# 11_mPCIe_CONN.net
KiCad netlist of a schematic drawn in Altium Designer
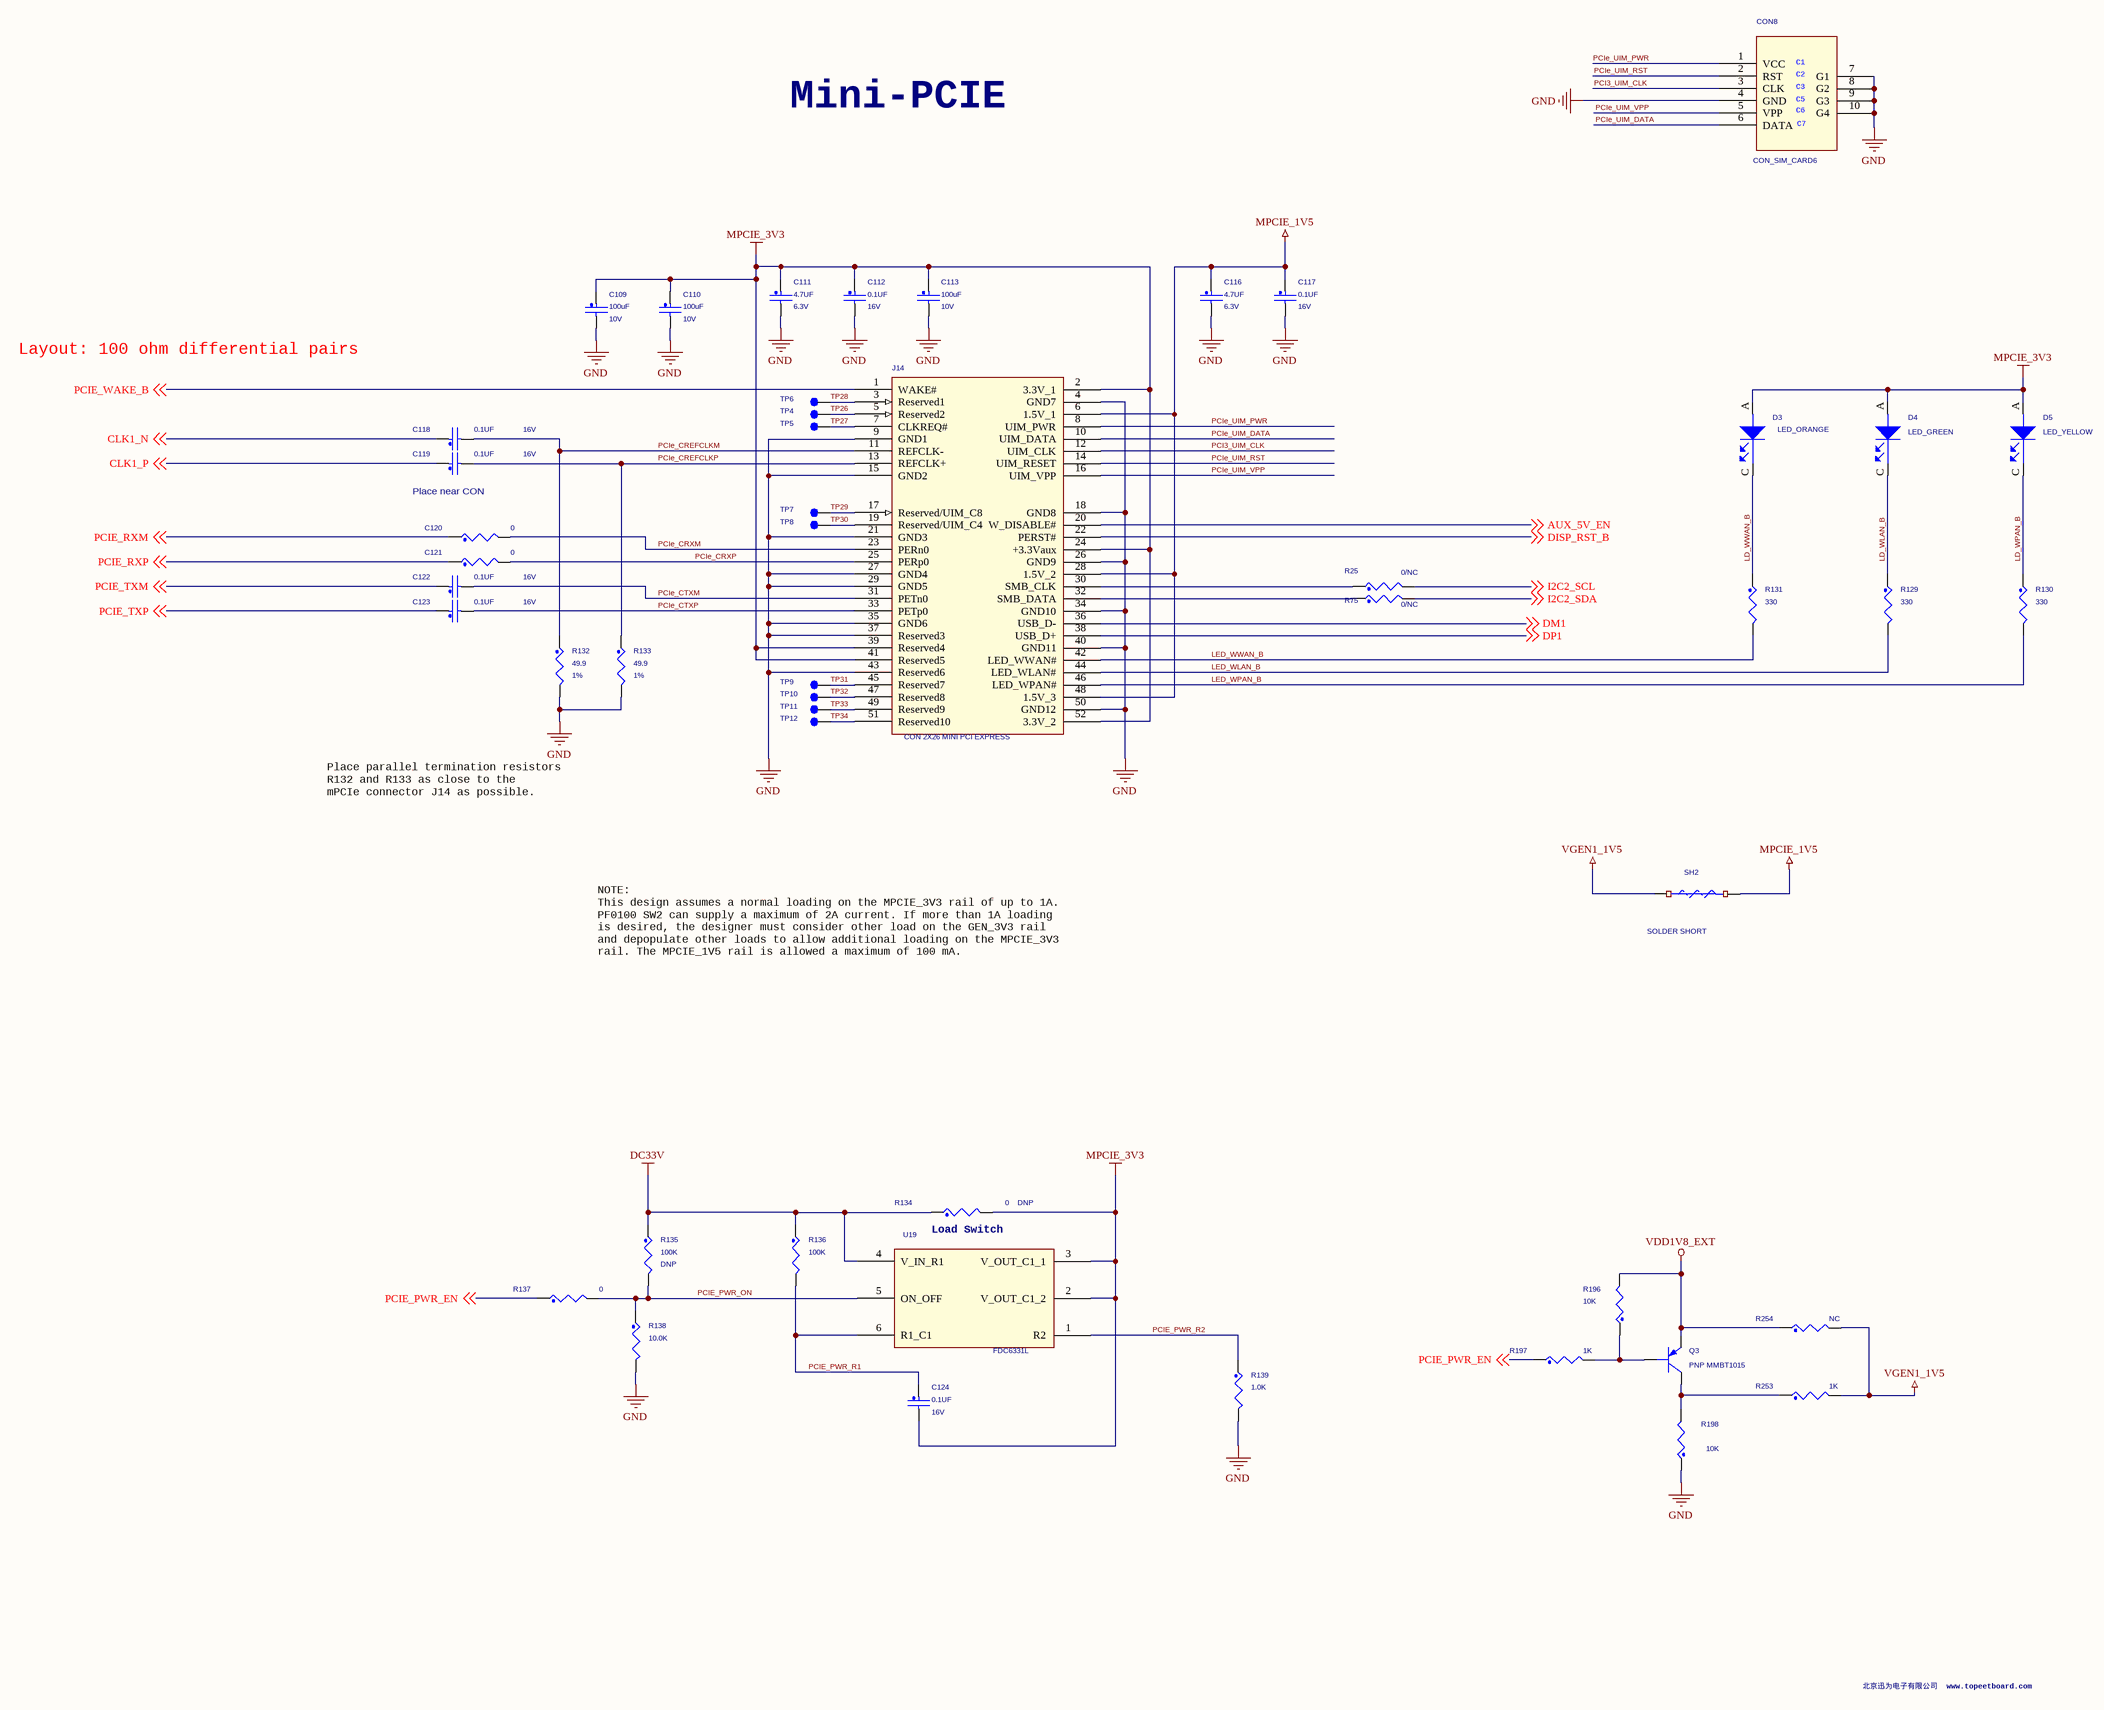
[diagram p0: 11 mPCIe CONN.SchDoc]

(export (version "E")
  (design (tool "Eeschema 10.0.6"))
  (components
    (comp (ref "C109")
      (value "100uF")
      (description "CAP CER 100uF 10V 20% X5R 1206")
      (fields (field (name "WVDC") "10V") (field (name "TOLERANCE") "20%") (field (name "VOLTAGE") "10V"))
      (libsource (lib "*") (part "CAP_NP"))
    )
    (comp (ref "C110")
      (value "100uF")
      (description "CAP CER 100uF 10V 20% X5R 1206")
      (fields (field (name "WVDC") "10V") (field (name "TOLERANCE") "20%") (field (name "VOLTAGE") "10V"))
      (libsource (lib "*") (part "CAP_NP"))
    )
    (comp (ref "C111")
      (value "4.7UF")
      (description "CAP CER 4.7UF 6.3V 10% X5R 0603")
      (fields (field (name "VOLTAGE") "6.3V") (field (name "TOLERANCE") "10%") (field (name "WVDC") "6.3V"))
      (libsource (lib "*") (part "CAP_NP"))
    )
    (comp (ref "C112")
      (value "0.1UF")
      (description "CAP CER 0.1UF 16V 10% X7R 0402")
      (fields (field (name "VOLTAGE") "16V") (field (name "TOLERANCE") "10%") (field (name "WVDC") "16V"))
      (libsource (lib "*") (part "CAP_NP"))
    )
    (comp (ref "C113")
      (value "100uF")
      (description "CAP CER 100uF 10V 20% X5R 1206")
      (fields (field (name "WVDC") "10V") (field (name "TOLERANCE") "20%") (field (name "VOLTAGE") "10V"))
      (libsource (lib "*") (part "CAP_NP"))
    )
    (comp (ref "C116")
      (value "4.7UF")
      (description "CAP CER 4.7UF 6.3V 10% X5R 0603")
      (fields (field (name "VOLTAGE") "6.3V") (field (name "TOLERANCE") "10%") (field (name "WVDC") "6.3V"))
      (libsource (lib "*") (part "CAP_NP"))
    )
    (comp (ref "C117")
      (value "0.1UF")
      (description "CAP CER 0.1UF 16V 10% X7R 0402")
      (fields (field (name "VOLTAGE") "16V") (field (name "WVDC") "16V") (field (name "TOLERANCE") "10%"))
      (libsource (lib "*") (part "CAP_NP"))
    )
    (comp (ref "C118")
      (value "0.1UF")
      (description "CAP CER 0.1UF 16V 10% X7R 0402")
      (fields (field (name "VOLTAGE") "16V") (field (name "WVDC") "16V") (field (name "TOLERANCE") "10%"))
      (libsource (lib "*") (part "CAP_NP"))
    )
    (comp (ref "C119")
      (value "0.1UF")
      (description "CAP CER 0.1UF 16V 10% X7R 0402")
      (fields (field (name "VOLTAGE") "16V") (field (name "WVDC") "16V") (field (name "TOLERANCE") "10%"))
      (libsource (lib "*") (part "CAP_NP"))
    )
    (comp (ref "C120")
      (value "0")
      (description "RES MF ZERO OHM 1/10W -- 0402")
      (libsource (lib "*") (part "RES_Dup1"))
    )
    (comp (ref "C121")
      (value "0")
      (description "RES MF ZERO OHM 1/10W -- 0402")
      (libsource (lib "*") (part "RES_Dup1"))
    )
    (comp (ref "C122")
      (value "0.1UF")
      (description "CAP CER 0.1UF 16V 10% X7R 0402")
      (fields (field (name "VOLTAGE") "16V") (field (name "WVDC") "16V") (field (name "TOLERANCE") "10%"))
      (libsource (lib "*") (part "CAP_NP"))
    )
    (comp (ref "C123")
      (value "0.1UF")
      (description "CAP CER 0.1UF 16V 10% X7R 0402")
      (fields (field (name "VOLTAGE") "16V") (field (name "WVDC") "16V") (field (name "TOLERANCE") "10%"))
      (libsource (lib "*") (part "CAP_NP"))
    )
    (comp (ref "C124")
      (value "0.1UF")
      (description "CAP CER 0.1UF 16V 10% X7R 0402")
      (fields (field (name "VOLTAGE") "16V") (field (name "TOLERANCE") "10%") (field (name "WVDC") "16V"))
      (libsource (lib "*") (part "CAP_NP"))
    )
    (comp (ref "CON8")
      (value "CON_SIM_CARD6")
      (footprint "SIM_CARD6")
      (libsource (lib "*") (part "CON_SIM_CARD6_2"))
    )
    (comp (ref "D3")
      (value "LED_ORANGE")
      (description "LED SUPER BRIGHT ORANGE SMD 0603")
      (libsource (lib "*") (part "LED"))
    )
    (comp (ref "D4")
      (value "LED_GREEN")
      (description "LED ULTRA-BRIGHT GREEN SMT 0603")
      (libsource (lib "*") (part "LED"))
    )
    (comp (ref "D5")
      (value "LED_YELLOW")
      (description "LED ULTRA-BRIGHT YELLOW 30MA 5V SMT 0603")
      (libsource (lib "*") (part "LED"))
    )
    (comp (ref "J14")
      (value "CON 2X26 MINI PCI EXPRESS")
      (description "CON 2X26 MINI PCI EXPRESS SMT 0.8MM SP 1136H")
      (libsource (lib "*") (part "MINI_PCI_LATCH_52P"))
    )
    (comp (ref "Q3") (value "PNP MMBT1015") (libsource (lib "*") (part "PNP ECB")))
    (comp (ref "R25")
      (value "0/NC")
      (description "RES MF 330 OHM 1/16W 1% AEC-Q200 0402")
      (fields (field (name "TOLERANCE") "1%"))
      (libsource (lib "*") (part "RES_Dup1"))
    )
    (comp (ref "R75")
      (value "0/NC")
      (description "RES MF 330 OHM 1/16W 1% AEC-Q200 0402")
      (fields (field (name "TOLERANCE") "1%"))
      (libsource (lib "*") (part "RES_Dup1"))
    )
    (comp (ref "R129")
      (value "330")
      (description "RES MF 330 OHM 1/16W 1% AEC-Q200 0402")
      (fields (field (name "TOLERANCE") "1%"))
      (libsource (lib "*") (part "RES_Dup1"))
    )
    (comp (ref "R130")
      (value "330")
      (description "RES MF 330 OHM 1/16W 1% AEC-Q200 0402")
      (fields (field (name "TOLERANCE") "1%"))
      (libsource (lib "*") (part "RES_Dup1"))
    )
    (comp (ref "R131")
      (value "330")
      (description "RES MF 330 OHM 1/16W 1% AEC-Q200 0402")
      (fields (field (name "TOLERANCE") "1%"))
      (libsource (lib "*") (part "RES_Dup1"))
    )
    (comp (ref "R132")
      (value "49.9")
      (description "RES MF 49.9 OHM 1/16W 1% 0402")
      (fields (field (name "TOLERANCE") "1%"))
      (libsource (lib "*") (part "RES_Dup1"))
    )
    (comp (ref "R133")
      (value "49.9")
      (description "RES MF 49.9 OHM 1/16W 1% 0402")
      (fields (field (name "TOLERANCE") "1%"))
      (libsource (lib "*") (part "RES_Dup1"))
    )
    (comp (ref "R134")
      (value "0")
      (description "RES MF ZERO OHM 1/10W -- 0402")
      (fields (field (name "ASSY_OPT") "DNP"))
      (libsource (lib "*") (part "RES_Dup1"))
    )
    (comp (ref "R135")
      (value "100K")
      (description "RES MF 100K 1/16W 1% 0402")
      (fields (field (name "TOLERANCE") "1%") (field (name "ASSY_OPT") "DNP"))
      (libsource (lib "*") (part "RES_Dup1"))
    )
    (comp (ref "R136")
      (value "100K")
      (description "RES MF 100K 1/16W 1% 0402")
      (fields (field (name "TOLERANCE") "1%"))
      (libsource (lib "*") (part "RES_Dup1"))
    )
    (comp (ref "R137")
      (value "0")
      (description "RES MF ZERO OHM 1/10W -- 0402")
      (libsource (lib "*") (part "RES_Dup1"))
    )
    (comp (ref "R138")
      (value "10.0K")
      (description "RES MF 10.0K 1/16W 1% AEC-Q200 0402")
      (fields (field (name "TOLERANCE") "1%"))
      (libsource (lib "*") (part "RES_Dup1"))
    )
    (comp (ref "R139")
      (value "1.0K")
      (description "RES MF 1.0K 1/16W 1% 0402")
      (fields (field (name "TOLERANCE") "1%"))
      (libsource (lib "*") (part "RES_Dup1"))
    )
    (comp (ref "R196")
      (value "10K")
      (description "RES MF ZERO OHM 1/10W -- 0402")
      (libsource (lib "*") (part "RES_Dup1"))
    )
    (comp (ref "R197")
      (value "1K")
      (description "RES MF ZERO OHM 1/10W -- 0402")
      (libsource (lib "*") (part "RES_Dup1"))
    )
    (comp (ref "R198")
      (value "10K")
      (description "RES MF ZERO OHM 1/10W -- 0402")
      (libsource (lib "*") (part "RES_Dup1"))
    )
    (comp (ref "R253")
      (value "1K")
      (description "RES MF ZERO OHM 1/10W -- 0402")
      (libsource (lib "*") (part "RES_Dup1"))
    )
    (comp (ref "R254")
      (value "NC")
      (description "RES MF ZERO OHM 1/10W -- 0402")
      (libsource (lib "*") (part "RES_Dup1"))
    )
    (comp (ref "SH2")
      (value "SOLDER SHORT")
      (description "SOLDER SHORT 0805  SMT NO PART TO ORDER")
      (libsource (lib "*") (part "RES_SHORT-2"))
    )
    (comp (ref "TP4")
      (value "TEST POINT")
      (description "TEST POINT PAD 35 MIL SMT, NO PART TO ORDER")
      (libsource (lib "*") (part "Test pad"))
    )
    (comp (ref "TP5")
      (value "TEST POINT")
      (description "TEST POINT PAD 35 MIL SMT, NO PART TO ORDER")
      (libsource (lib "*") (part "Test pad"))
    )
    (comp (ref "TP6")
      (value "TEST POINT")
      (description "TEST POINT PAD 35 MIL SMT, NO PART TO ORDER")
      (libsource (lib "*") (part "Test pad"))
    )
    (comp (ref "TP7")
      (value "TEST POINT")
      (description "TEST POINT PAD 35 MIL SMT, NO PART TO ORDER")
      (libsource (lib "*") (part "Test pad"))
    )
    (comp (ref "TP8")
      (value "TEST POINT")
      (description "TEST POINT PAD 35 MIL SMT, NO PART TO ORDER")
      (libsource (lib "*") (part "Test pad"))
    )
    (comp (ref "TP9")
      (value "TEST POINT")
      (description "TEST POINT PAD 35 MIL SMT, NO PART TO ORDER")
      (libsource (lib "*") (part "Test pad"))
    )
    (comp (ref "TP10")
      (value "TEST POINT")
      (description "TEST POINT PAD 35 MIL SMT, NO PART TO ORDER")
      (libsource (lib "*") (part "Test pad"))
    )
    (comp (ref "TP11")
      (value "TEST POINT")
      (description "TEST POINT PAD 35 MIL SMT, NO PART TO ORDER")
      (libsource (lib "*") (part "Test pad"))
    )
    (comp (ref "TP12")
      (value "TEST POINT")
      (description "TEST POINT PAD 35 MIL SMT, NO PART TO ORDER")
      (libsource (lib "*") (part "Test pad"))
    )
    (comp (ref "U19")
      (value "FDC6331L")
      (description "IC LOAD SW 2.5-8V SSOT6")
      (libsource (lib "*") (part "FDC6331L"))
    )
  )
  (nets
    (net (code "1") (name "/LD_WLAN_B") (class "Default")
      (node (ref "D4") (pin "C") (pinfunction "CATHODE_C") (pintype "passive"))
      (node (ref "R129") (pin "1") (pinfunction "1_1") (pintype "passive"))
    )
    (net (code "2") (name "/LD_WPAN_B") (class "Default")
      (node (ref "D5") (pin "C") (pinfunction "CATHODE_C") (pintype "passive"))
      (node (ref "R130") (pin "1") (pinfunction "1_1") (pintype "passive"))
    )
    (net (code "3") (name "/LD_WWAN_B") (class "Default")
      (node (ref "D3") (pin "C") (pinfunction "CATHODE_C") (pintype "passive"))
      (node (ref "R131") (pin "1") (pinfunction "1_1") (pintype "passive"))
    )
    (net (code "4") (name "/LED_WLAN_B") (class "Default")
      (node (ref "J14") (pin "44") (pinfunction "LED_WLAN#_44") (pintype "passive"))
      (node (ref "R129") (pin "2") (pinfunction "2_2") (pintype "passive"))
    )
    (net (code "5") (name "/LED_WPAN_B") (class "Default")
      (node (ref "J14") (pin "46") (pinfunction "LED_WPAN#_46") (pintype "passive"))
      (node (ref "R130") (pin "2") (pinfunction "2_2") (pintype "passive"))
    )
    (net (code "6") (name "/LED_WWAN_B") (class "Default")
      (node (ref "J14") (pin "42") (pinfunction "LED_WWAN#_42") (pintype "passive"))
      (node (ref "R131") (pin "2") (pinfunction "2_2") (pintype "passive"))
    )
    (net (code "7") (name "/PCI3_UIM_CLK") (class "Default")
      (node (ref "CON8") (pin "3") (pinfunction "CLK_3") (pintype "passive"))
      (node (ref "J14") (pin "12") (pinfunction "UIM_CLK_12") (pintype "passive"))
    )
    (net (code "8") (name "/PCIE_PWR_ON") (class "Default")
      (node (ref "R135") (pin "2") (pinfunction "2_2") (pintype "passive"))
      (node (ref "R137") (pin "2") (pinfunction "2_2") (pintype "passive"))
      (node (ref "R138") (pin "1") (pinfunction "1_1") (pintype "passive"))
      (node (ref "U19") (pin "5") (pinfunction "ON_OFF_5") (pintype "passive"))
    )
    (net (code "9") (name "/PCIE_PWR_R1") (class "Default")
      (node (ref "C124") (pin "1") (pinfunction "1_1") (pintype "passive"))
      (node (ref "R136") (pin "2") (pinfunction "2_2") (pintype "passive"))
      (node (ref "U19") (pin "6") (pinfunction "R1_C1_6") (pintype "passive"))
    )
    (net (code "10") (name "/PCIE_PWR_R2") (class "Default")
      (node (ref "R139") (pin "1") (pinfunction "1_1") (pintype "passive"))
      (node (ref "U19") (pin "1") (pinfunction "R2_1") (pintype "passive"))
    )
    (net (code "11") (name "/PCIe_CREFCLKM") (class "Default")
      (node (ref "C118") (pin "2") (pinfunction "2_2") (pintype "passive"))
      (node (ref "J14") (pin "11") (pinfunction "REFCLK-_11") (pintype "passive"))
      (node (ref "R132") (pin "1") (pinfunction "1_1") (pintype "passive"))
    )
    (net (code "12") (name "/PCIe_CREFCLKP") (class "Default")
      (node (ref "C119") (pin "2") (pinfunction "2_2") (pintype "passive"))
      (node (ref "J14") (pin "13") (pinfunction "REFCLK+_13") (pintype "passive"))
      (node (ref "R133") (pin "1") (pinfunction "1_1") (pintype "passive"))
    )
    (net (code "13") (name "/PCIe_CRXM") (class "Default")
      (node (ref "C120") (pin "2") (pinfunction "2_2") (pintype "passive"))
      (node (ref "J14") (pin "23") (pinfunction "PERn0_23") (pintype "passive"))
    )
    (net (code "14") (name "/PCIe_CRXP") (class "Default")
      (node (ref "C121") (pin "2") (pinfunction "2_2") (pintype "passive"))
      (node (ref "J14") (pin "25") (pinfunction "PERp0_25") (pintype "passive"))
    )
    (net (code "15") (name "/PCIe_CTXM") (class "Default")
      (node (ref "C122") (pin "2") (pinfunction "2_2") (pintype "passive"))
      (node (ref "J14") (pin "31") (pinfunction "PETn0_31") (pintype "passive"))
    )
    (net (code "16") (name "/PCIe_CTXP") (class "Default")
      (node (ref "C123") (pin "2") (pinfunction "2_2") (pintype "passive"))
      (node (ref "J14") (pin "33") (pinfunction "PETp0_33") (pintype "passive"))
    )
    (net (code "17") (name "/PCIe_UIM_DATA") (class "Default")
      (node (ref "CON8") (pin "6") (pinfunction "DATA_6") (pintype "passive"))
      (node (ref "J14") (pin "10") (pinfunction "UIM_DATA_10") (pintype "passive"))
    )
    (net (code "18") (name "/PCIe_UIM_PWR") (class "Default")
      (node (ref "CON8") (pin "1") (pinfunction "VCC_1") (pintype "passive"))
      (node (ref "J14") (pin "8") (pinfunction "UIM_PWR_8") (pintype "passive"))
    )
    (net (code "19") (name "/PCIe_UIM_RST") (class "Default")
      (node (ref "CON8") (pin "2") (pinfunction "RST_2") (pintype "passive"))
      (node (ref "J14") (pin "14") (pinfunction "UIM_RESET_14") (pintype "passive"))
    )
    (net (code "20") (name "/PCIe_UIM_VPP") (class "Default")
      (node (ref "CON8") (pin "5") (pinfunction "VPP_5") (pintype "passive"))
      (node (ref "J14") (pin "16") (pinfunction "UIM_VPP_16") (pintype "passive"))
    )
    (net (code "21") (name "/TP26") (class "Default")
      (node (ref "J14") (pin "5") (pinfunction "Reserved2_5") (pintype "input"))
      (node (ref "TP4") (pin "1") (pinfunction "Pin1_1") (pintype "passive"))
    )
    (net (code "22") (name "/TP27") (class "Default")
      (node (ref "J14") (pin "7") (pinfunction "CLKREQ#_7") (pintype "passive"))
      (node (ref "TP5") (pin "1") (pinfunction "Pin1_1") (pintype "passive"))
    )
    (net (code "23") (name "/TP28") (class "Default")
      (node (ref "J14") (pin "3") (pinfunction "Reserved1_3") (pintype "input"))
      (node (ref "TP6") (pin "1") (pinfunction "Pin1_1") (pintype "passive"))
    )
    (net (code "24") (name "/TP29") (class "Default")
      (node (ref "J14") (pin "17") (pinfunction "Reserved/UIM_C8_17") (pintype "input"))
      (node (ref "TP7") (pin "1") (pinfunction "Pin1_1") (pintype "passive"))
    )
    (net (code "25") (name "/TP30") (class "Default")
      (node (ref "J14") (pin "19") (pinfunction "Reserved/UIM_C4_19") (pintype "passive"))
      (node (ref "TP8") (pin "1") (pinfunction "Pin1_1") (pintype "passive"))
    )
    (net (code "26") (name "/TP31") (class "Default")
      (node (ref "J14") (pin "45") (pinfunction "Reserved7_45") (pintype "passive"))
      (node (ref "TP9") (pin "1") (pinfunction "Pin1_1") (pintype "passive"))
    )
    (net (code "27") (name "/TP32") (class "Default")
      (node (ref "J14") (pin "47") (pinfunction "Reserved8_47") (pintype "passive"))
      (node (ref "TP10") (pin "1") (pinfunction "Pin1_1") (pintype "passive"))
    )
    (net (code "28") (name "/TP33") (class "Default")
      (node (ref "J14") (pin "49") (pinfunction "Reserved9_49") (pintype "passive"))
      (node (ref "TP11") (pin "1") (pinfunction "Pin1_1") (pintype "passive"))
    )
    (net (code "29") (name "/TP34") (class "Default")
      (node (ref "J14") (pin "51") (pinfunction "Reserved10_51") (pintype "passive"))
      (node (ref "TP12") (pin "1") (pinfunction "Pin1_1") (pintype "passive"))
    )
    (net (code "30") (name "AUX_5V_EN") (class "Default")
      (node (ref "J14") (pin "20") (pinfunction "W_DISABLE#_20") (pintype "passive"))
    )
    (net (code "31") (name "CLK1_N") (class "Default")
      (node (ref "C118") (pin "1") (pinfunction "1_1") (pintype "passive"))
    )
    (net (code "32") (name "CLK1_P") (class "Default")
      (node (ref "C119") (pin "1") (pinfunction "1_1") (pintype "passive"))
    )
    (net (code "33") (name "DC33V") (class "Default")
      (node (ref "R134") (pin "1") (pinfunction "1_1") (pintype "passive"))
      (node (ref "R135") (pin "1") (pinfunction "1_1") (pintype "passive"))
      (node (ref "R136") (pin "1") (pinfunction "1_1") (pintype "passive"))
      (node (ref "U19") (pin "4") (pinfunction "V_IN_R1_4") (pintype "passive"))
    )
    (net (code "34") (name "DISP_RST_B") (class "Default")
      (node (ref "J14") (pin "22") (pinfunction "PERST#_22") (pintype "passive"))
    )
    (net (code "35") (name "DM1") (class "Default")
      (node (ref "J14") (pin "36") (pinfunction "USB_D-_36") (pintype "passive"))
    )
    (net (code "36") (name "DP1") (class "Default")
      (node (ref "J14") (pin "38") (pinfunction "USB_D+_38") (pintype "passive"))
    )
    (net (code "37") (name "GND") (class "Default")
      (node (ref "C109") (pin "2") (pinfunction "2_2") (pintype "passive"))
      (node (ref "C110") (pin "2") (pinfunction "2_2") (pintype "passive"))
      (node (ref "C111") (pin "2") (pinfunction "2_2") (pintype "passive"))
      (node (ref "C112") (pin "2") (pinfunction "2_2") (pintype "passive"))
      (node (ref "C113") (pin "2") (pinfunction "2_2") (pintype "passive"))
      (node (ref "C116") (pin "2") (pinfunction "2_2") (pintype "passive"))
      (node (ref "C117") (pin "2") (pinfunction "2_2") (pintype "passive"))
      (node (ref "CON8") (pin "10") (pinfunction "G4_10") (pintype "passive"))
      (node (ref "CON8") (pin "4") (pinfunction "GND_4") (pintype "passive"))
      (node (ref "CON8") (pin "7") (pinfunction "G1_7") (pintype "passive"))
      (node (ref "CON8") (pin "8") (pinfunction "G2_8") (pintype "passive"))
      (node (ref "CON8") (pin "9") (pinfunction "G3_9") (pintype "passive"))
      (node (ref "J14") (pin "15") (pinfunction "GND2_15") (pintype "passive"))
      (node (ref "J14") (pin "18") (pinfunction "GND8_18") (pintype "passive"))
      (node (ref "J14") (pin "21") (pinfunction "GND3_21") (pintype "passive"))
      (node (ref "J14") (pin "26") (pinfunction "GND9_26") (pintype "passive"))
      (node (ref "J14") (pin "27") (pinfunction "GND4_27") (pintype "passive"))
      (node (ref "J14") (pin "29") (pinfunction "GND5_29") (pintype "passive"))
      (node (ref "J14") (pin "34") (pinfunction "GND10_34") (pintype "passive"))
      (node (ref "J14") (pin "35") (pinfunction "GND6_35") (pintype "passive"))
      (node (ref "J14") (pin "37") (pinfunction "Reserved3_37") (pintype "passive"))
      (node (ref "J14") (pin "4") (pinfunction "GND7_4") (pintype "passive"))
      (node (ref "J14") (pin "40") (pinfunction "GND11_40") (pintype "passive"))
      (node (ref "J14") (pin "43") (pinfunction "Reserved6_43") (pintype "passive"))
      (node (ref "J14") (pin "50") (pinfunction "GND12_50") (pintype "passive"))
      (node (ref "J14") (pin "9") (pinfunction "GND1_9") (pintype "passive"))
      (node (ref "R132") (pin "2") (pinfunction "2_2") (pintype "passive"))
      (node (ref "R133") (pin "2") (pinfunction "2_2") (pintype "passive"))
      (node (ref "R138") (pin "2") (pinfunction "2_2") (pintype "passive"))
      (node (ref "R139") (pin "2") (pinfunction "2_2") (pintype "passive"))
      (node (ref "R198") (pin "1") (pinfunction "1_1") (pintype "passive"))
    )
    (net (code "38") (name "I2C2_SCL") (class "Default")
      (node (ref "R25") (pin "2") (pinfunction "2_2") (pintype "passive"))
    )
    (net (code "39") (name "I2C2_SDA") (class "Default")
      (node (ref "R75") (pin "2") (pinfunction "2_2") (pintype "passive"))
    )
    (net (code "40") (name "MPCIE_1V5") (class "Default")
      (node (ref "C116") (pin "1") (pinfunction "1_1") (pintype "passive"))
      (node (ref "C117") (pin "1") (pinfunction "1_1") (pintype "passive"))
      (node (ref "J14") (pin "28") (pinfunction "1.5V_2_28") (pintype "passive"))
      (node (ref "J14") (pin "48") (pinfunction "1.5V_3_48") (pintype "passive"))
      (node (ref "J14") (pin "6") (pinfunction "1.5V_1_6") (pintype "passive"))
      (node (ref "SH2") (pin "2") (pinfunction "2_2") (pintype "passive"))
    )
    (net (code "41") (name "MPCIE_3V3") (class "Default")
      (node (ref "C109") (pin "1") (pinfunction "1_1") (pintype "passive"))
      (node (ref "C110") (pin "1") (pinfunction "1_1") (pintype "passive"))
      (node (ref "C111") (pin "1") (pinfunction "1_1") (pintype "passive"))
      (node (ref "C112") (pin "1") (pinfunction "1_1") (pintype "passive"))
      (node (ref "C113") (pin "1") (pinfunction "1_1") (pintype "passive"))
      (node (ref "C124") (pin "2") (pinfunction "2_2") (pintype "passive"))
      (node (ref "D3") (pin "A") (pinfunction "ANODE_A") (pintype "passive"))
      (node (ref "D4") (pin "A") (pinfunction "ANODE_A") (pintype "passive"))
      (node (ref "D5") (pin "A") (pinfunction "ANODE_A") (pintype "passive"))
      (node (ref "J14") (pin "2") (pinfunction "3.3V_1_2") (pintype "passive"))
      (node (ref "J14") (pin "24") (pinfunction "+3.3Vaux_24") (pintype "passive"))
      (node (ref "J14") (pin "39") (pinfunction "Reserved4_39") (pintype "passive"))
      (node (ref "J14") (pin "41") (pinfunction "Reserved5_41") (pintype "passive"))
      (node (ref "J14") (pin "52") (pinfunction "3.3V_2_52") (pintype "passive"))
      (node (ref "R134") (pin "2") (pinfunction "2_2") (pintype "passive"))
      (node (ref "U19") (pin "2") (pinfunction "V_OUT_C1_2_2") (pintype "passive"))
      (node (ref "U19") (pin "3") (pinfunction "V_OUT_C1_1_3") (pintype "passive"))
    )
    (net (code "42") (name "Net-(J14-SMB_CLK)") (class "Default")
      (node (ref "J14") (pin "30") (pinfunction "SMB_CLK_30") (pintype "passive"))
      (node (ref "R25") (pin "1") (pinfunction "1_1") (pintype "passive"))
    )
    (net (code "43") (name "Net-(J14-SMB_DATA)") (class "Default")
      (node (ref "J14") (pin "32") (pinfunction "SMB_DATA_32") (pintype "passive"))
      (node (ref "R75") (pin "1") (pinfunction "1_1") (pintype "passive"))
    )
    (net (code "44") (name "Net-(Q3-B)") (class "Default")
      (node (ref "Q3") (pin "3") (pinfunction "B_3") (pintype "passive"))
      (node (ref "R196") (pin "1") (pinfunction "1_1") (pintype "passive"))
      (node (ref "R197") (pin "2") (pinfunction "2_2") (pintype "passive"))
    )
    (net (code "45") (name "Net-(Q3-C)") (class "Default")
      (node (ref "Q3") (pin "2") (pinfunction "C_2") (pintype "passive"))
      (node (ref "R198") (pin "2") (pinfunction "2_2") (pintype "passive"))
      (node (ref "R253") (pin "1") (pinfunction "1_1") (pintype "passive"))
    )
    (net (code "46") (name "PCIE_PWR_EN") (class "Default")
      (node (ref "R137") (pin "1") (pinfunction "1_1") (pintype "passive"))
      (node (ref "R197") (pin "1") (pinfunction "1_1") (pintype "passive"))
    )
    (net (code "47") (name "PCIE_RXM") (class "Default")
      (node (ref "C120") (pin "1") (pinfunction "1_1") (pintype "passive"))
    )
    (net (code "48") (name "PCIE_RXP") (class "Default")
      (node (ref "C121") (pin "1") (pinfunction "1_1") (pintype "passive"))
    )
    (net (code "49") (name "PCIE_TXM") (class "Default")
      (node (ref "C122") (pin "1") (pinfunction "1_1") (pintype "passive"))
    )
    (net (code "50") (name "PCIE_TXP") (class "Default")
      (node (ref "C123") (pin "1") (pinfunction "1_1") (pintype "passive"))
    )
    (net (code "51") (name "PCIE_WAKE_B") (class "Default")
      (node (ref "J14") (pin "1") (pinfunction "WAKE#_1") (pintype "passive"))
    )
    (net (code "52") (name "VDD1V8_EXT") (class "Default")
      (node (ref "Q3") (pin "1") (pinfunction "E_1") (pintype "passive"))
      (node (ref "R196") (pin "2") (pinfunction "2_2") (pintype "passive"))
      (node (ref "R254") (pin "1") (pinfunction "1_1") (pintype "passive"))
    )
    (net (code "53") (name "VGEN1_1V5") (class "Default")
      (node (ref "R253") (pin "2") (pinfunction "2_2") (pintype "passive"))
      (node (ref "R254") (pin "2") (pinfunction "2_2") (pintype "passive"))
      (node (ref "SH2") (pin "1") (pinfunction "1_1") (pintype "passive"))
    )
  )
)
